# SCH_Nucleo__DAC8830_ADS8681_2022-10-27.net
KiCad netlist of a schematic drawn in EasyEDA
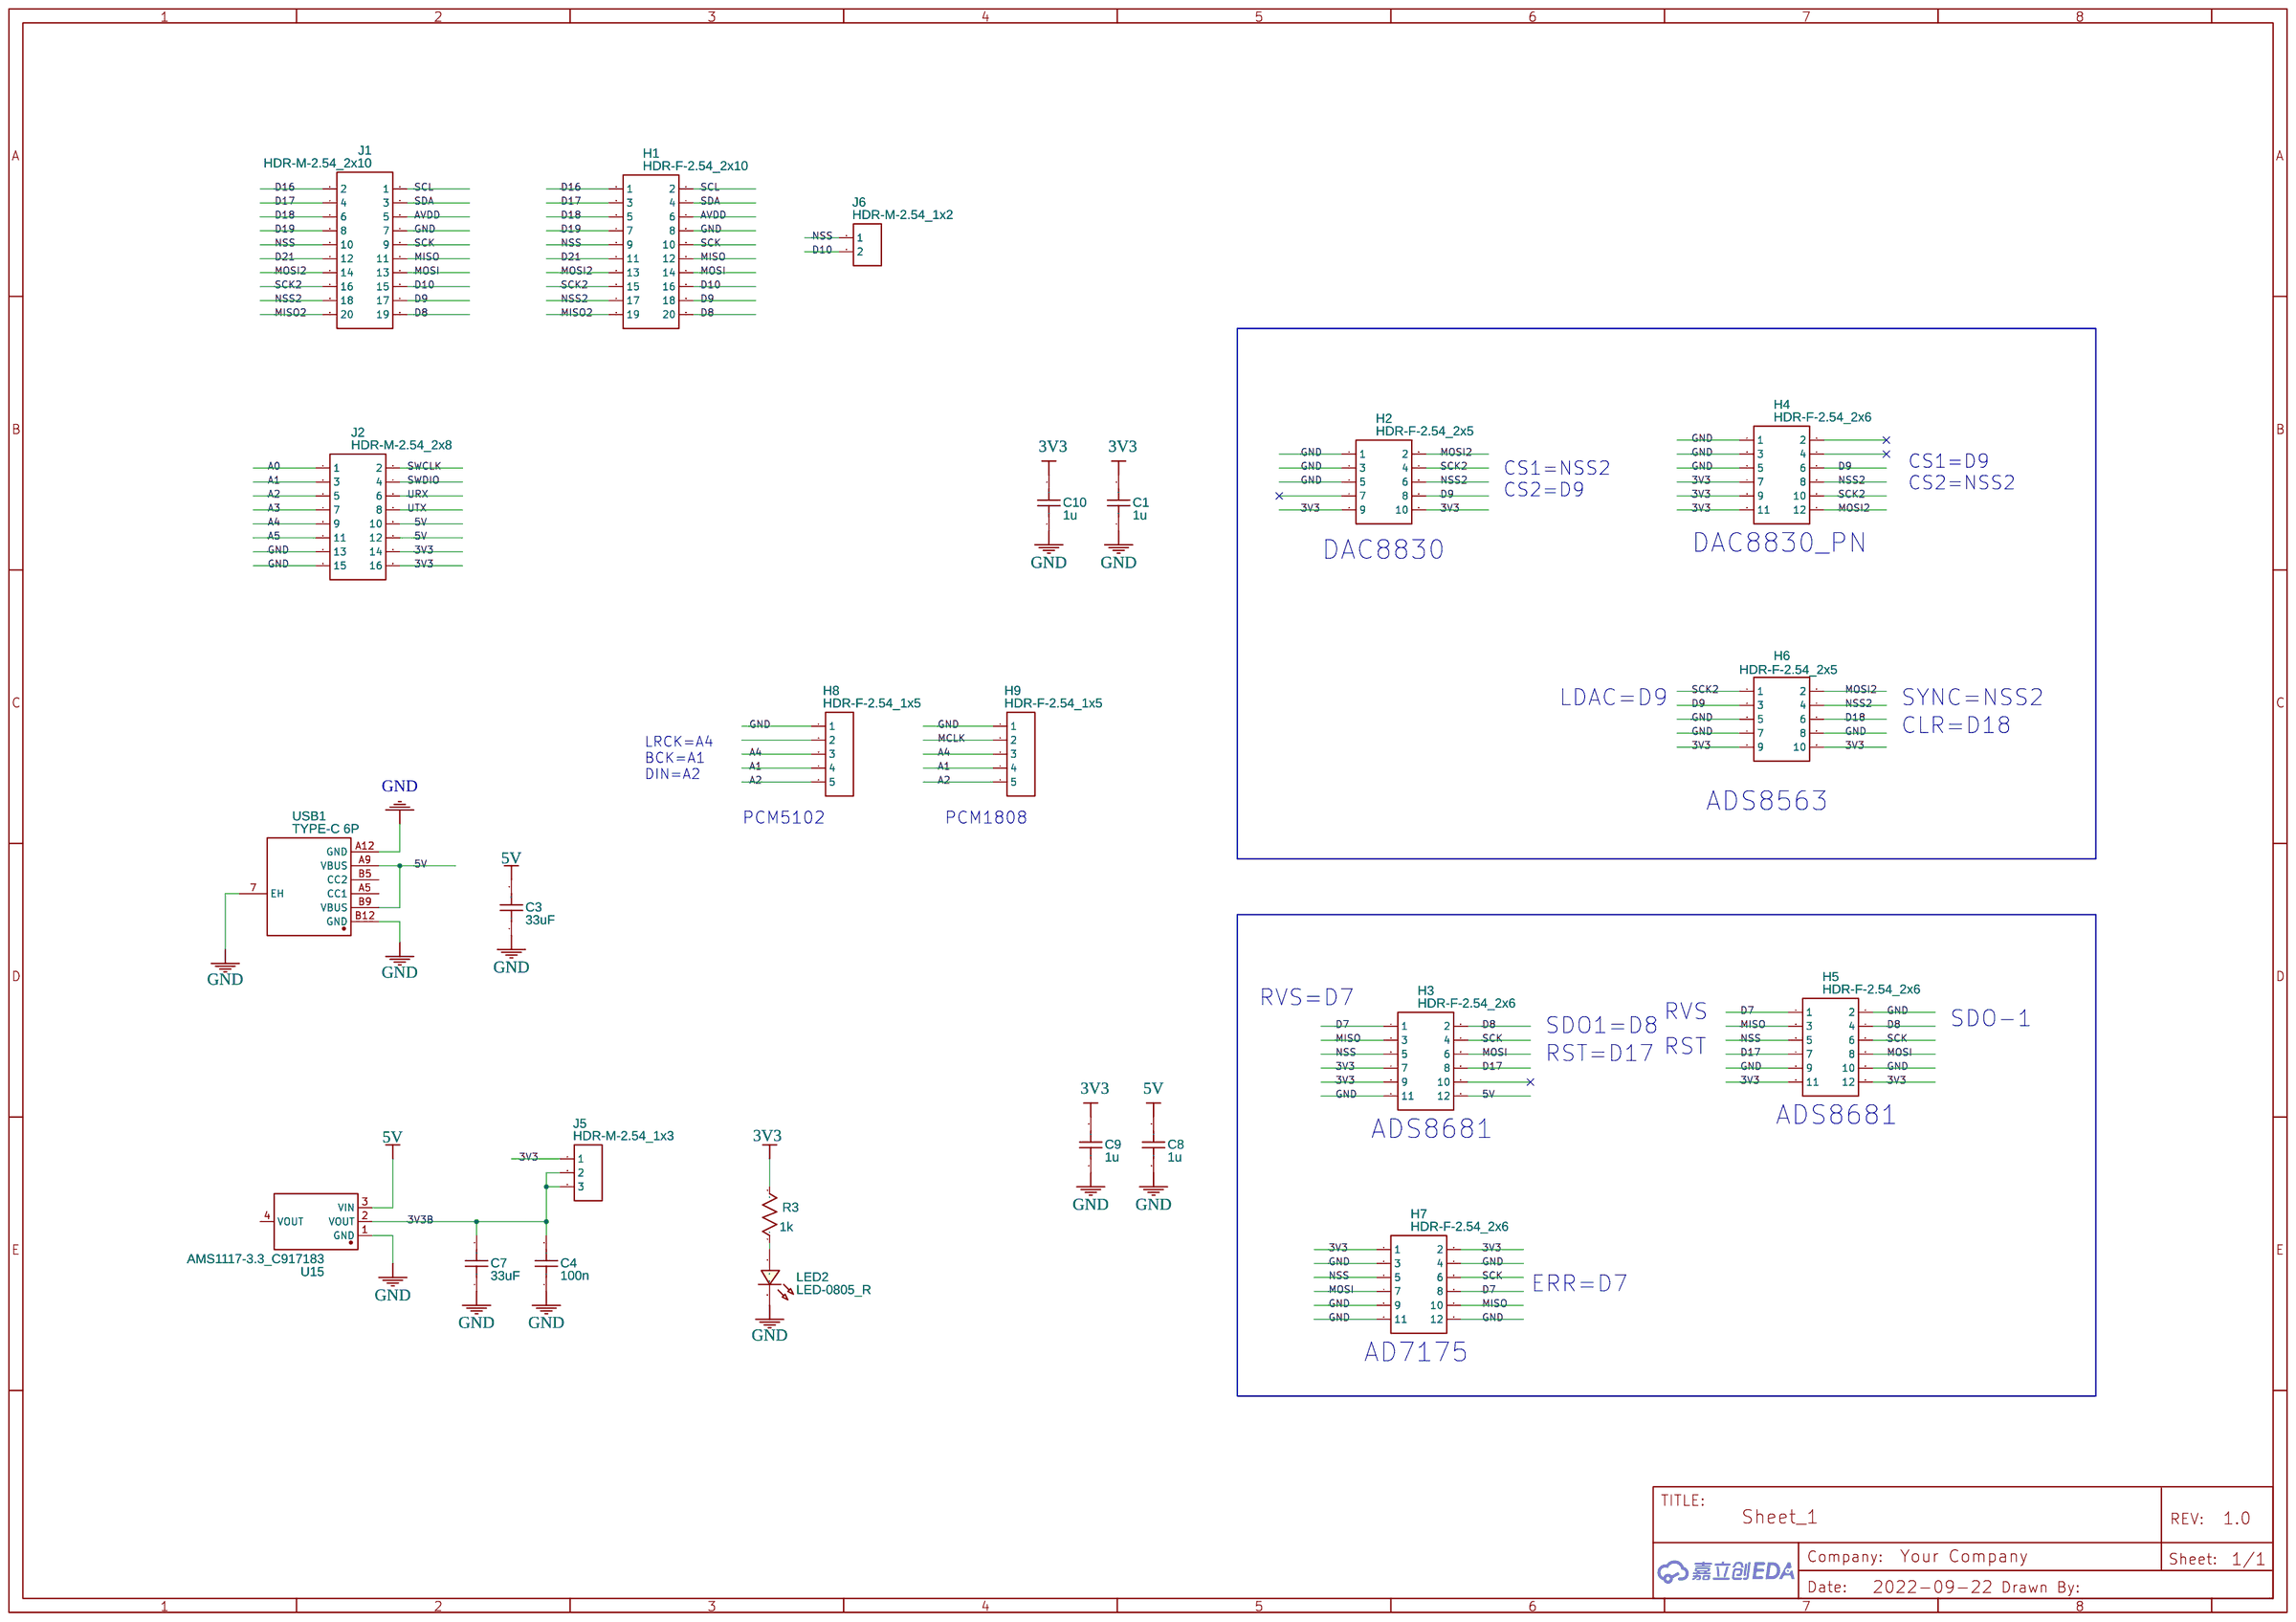
[diagram p0: 连接器]
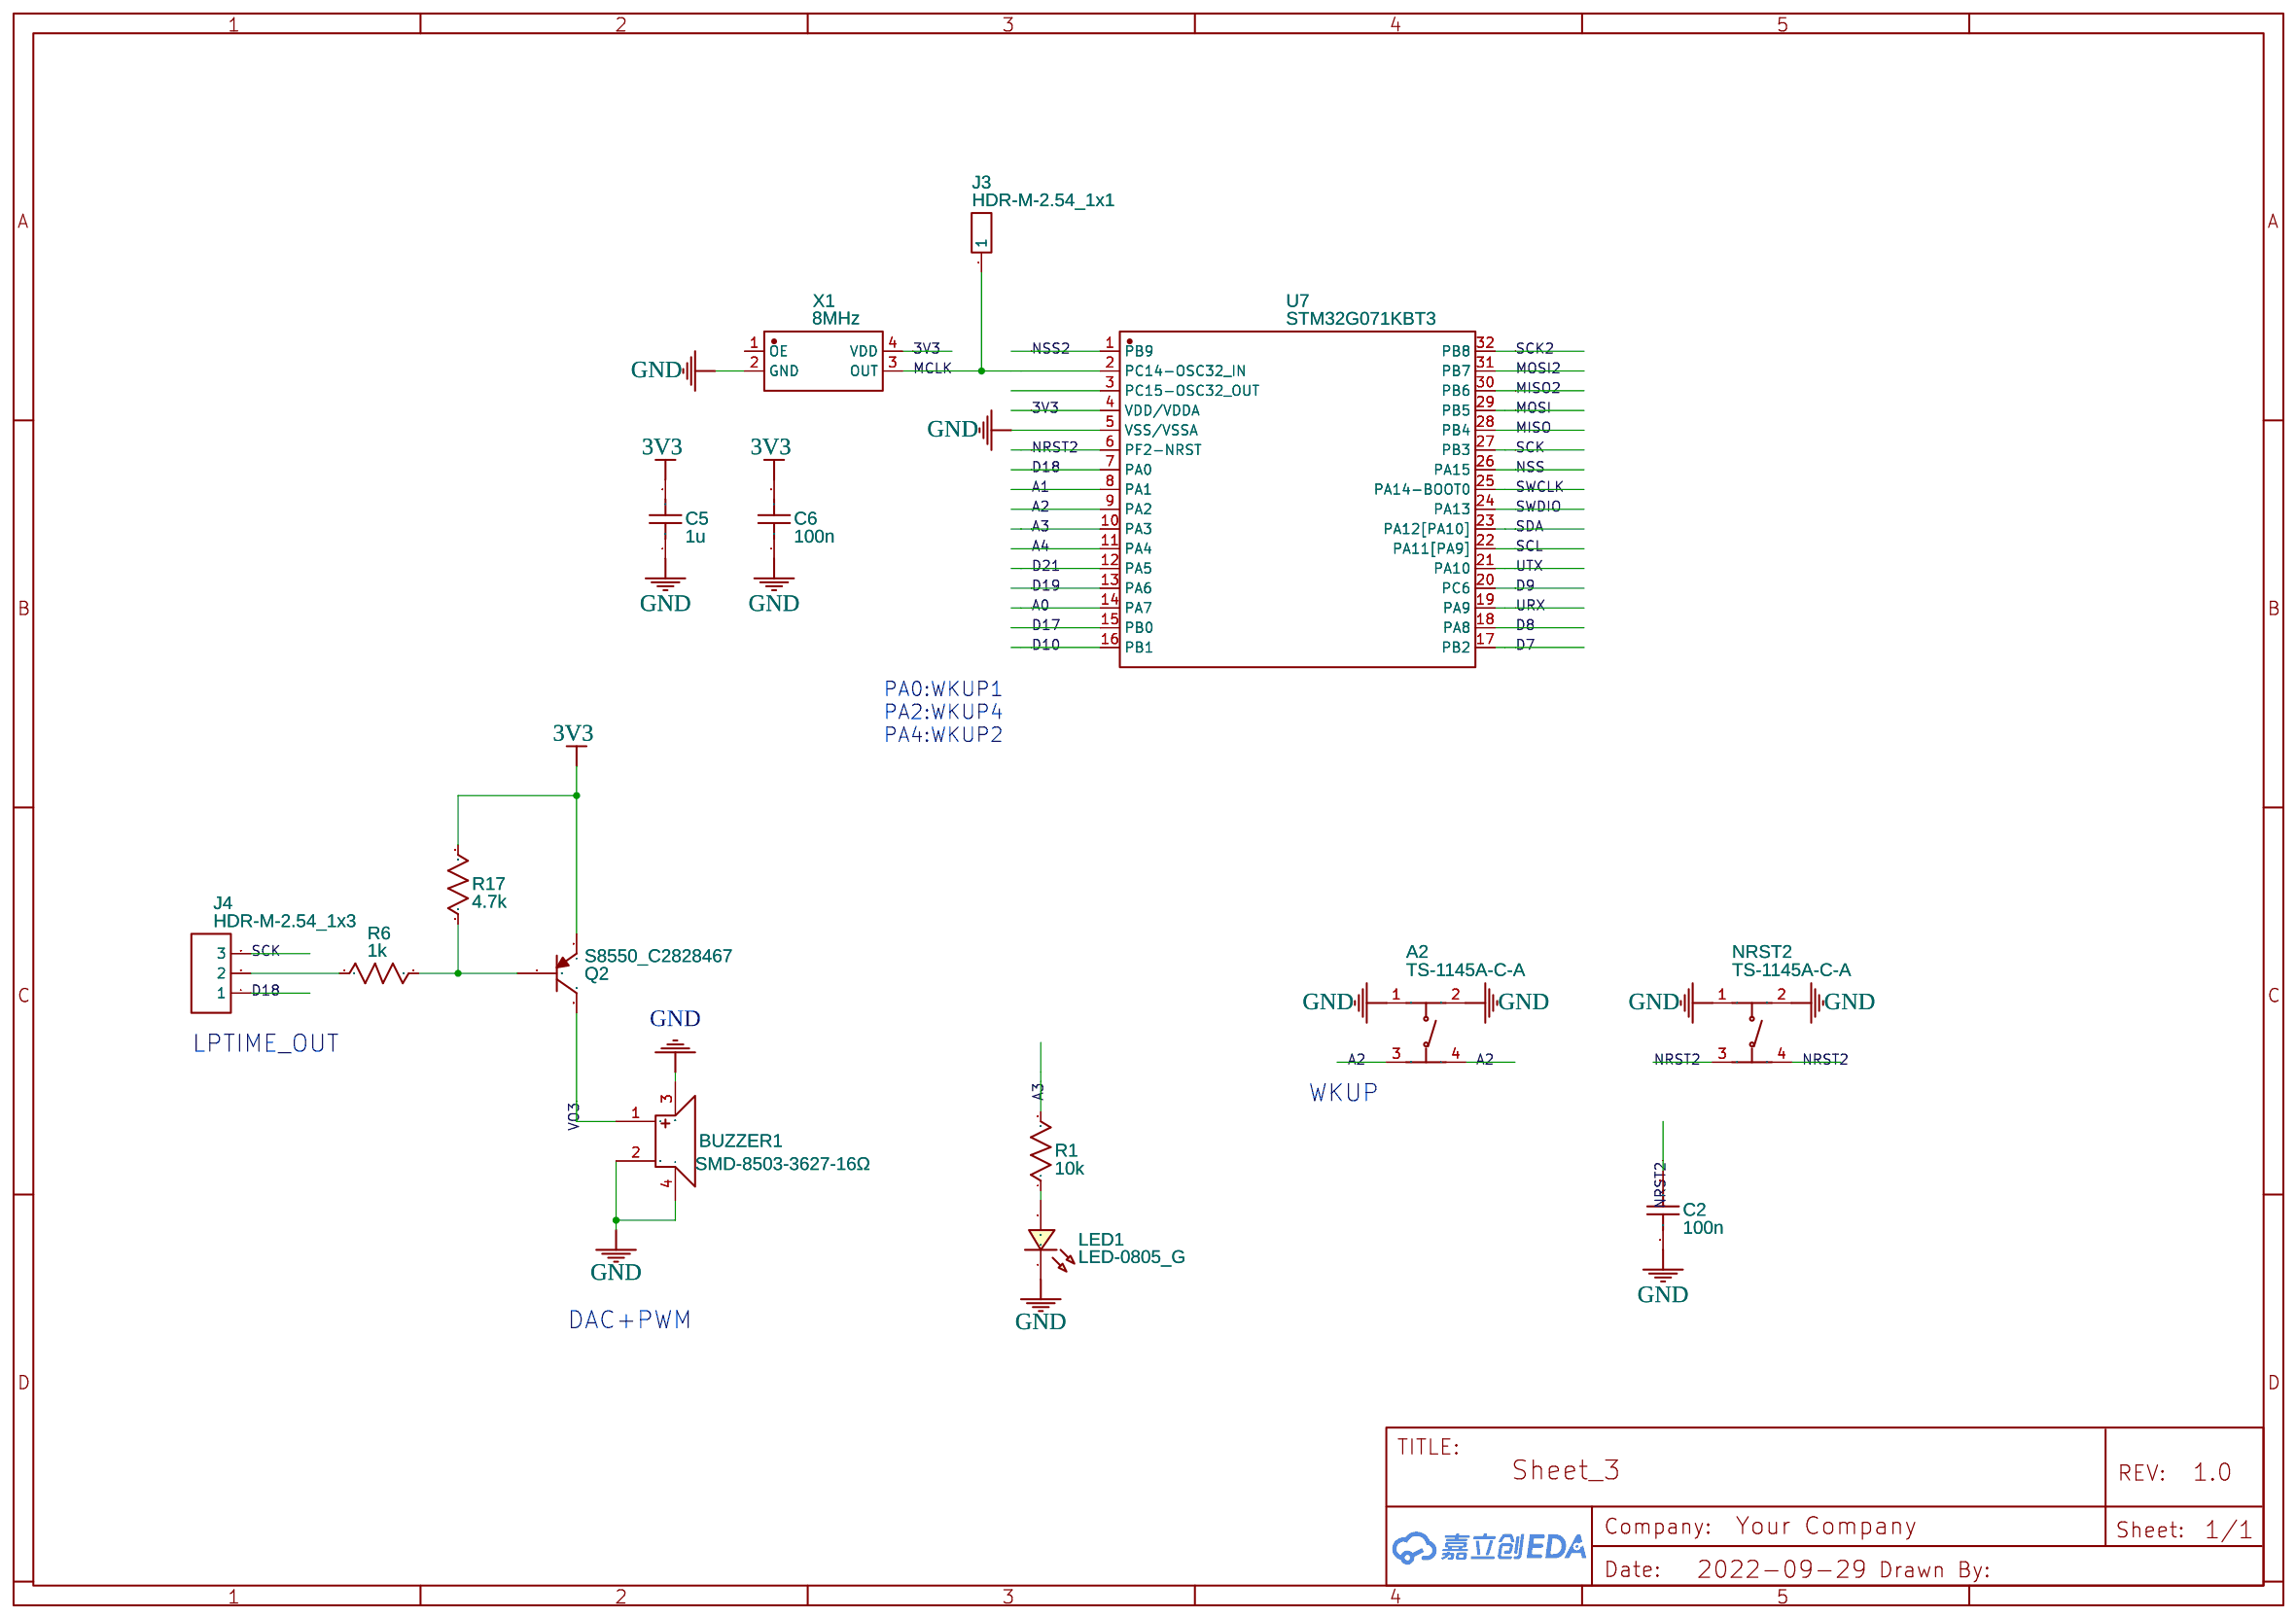
[diagram p1: mcu]

(export (version "E")
  (design (tool "Eeschema 10.0.6"))
  (components
    (comp (ref "C1")
      (value "1u")
      (fields
        (field (name "BOM_Manufacturer Part") "0805B105M500NT")
        (field (name "BOM_Supplier Part") "C2913555")
      )
      (libsource (lib "") (part "C_0805_US"))
    )
    (comp (ref "C3")
      (value "33uF")
      (fields
        (field (name "BOM_Manufacturer Part") "C3225X5R0J336MT0A0N")
        (field (name "BOM_Supplier Part") "C695362")
      )
      (libsource (lib "") (part "C3225X5R0J336MT0A0N"))
    )
    (comp (ref "C4") (value "100n") (libsource (lib "") (part "C_0805_US")))
    (comp (ref "C7")
      (value "33uF")
      (fields
        (field (name "BOM_Manufacturer Part") "C3225X5R0J336MT0A0N")
        (field (name "BOM_Supplier Part") "C695362")
      )
      (libsource (lib "") (part "C3225X5R0J336MT0A0N"))
    )
    (comp (ref "C8")
      (value "1u")
      (fields
        (field (name "BOM_Manufacturer Part") "0805B105M500NT")
        (field (name "BOM_Supplier Part") "C2913555")
      )
      (libsource (lib "") (part "C_0805_US"))
    )
    (comp (ref "C9")
      (value "1u")
      (fields
        (field (name "BOM_Manufacturer Part") "0805B105M500NT")
        (field (name "BOM_Supplier Part") "C2913555")
      )
      (libsource (lib "") (part "C_0805_US"))
    )
    (comp (ref "C10")
      (value "1u")
      (fields
        (field (name "BOM_Manufacturer Part") "0805B105M500NT")
        (field (name "BOM_Supplier Part") "C2913555")
      )
      (libsource (lib "") (part "C_0805_US"))
    )
    (comp (ref "H1")
      (value "HDR-F-2.54_2x10")
      (fields (field (name "BOM_Supplier Part") "C30867"))
      (libsource (lib "") (part "HDR-F-2.54_2x10"))
    )
    (comp (ref "H2")
      (value "HDR-F-2.54_2x5")
      (fields (field (name "BOM_Supplier Part") "C30419"))
      (libsource (lib "") (part "HDR-F-2.54_2x5"))
    )
    (comp (ref "H3")
      (value "HDR-F-2.54_2x6")
      (fields (field (name "BOM_Supplier Part") "C36191"))
      (libsource (lib "") (part "HDR-F-2.54_2x6"))
    )
    (comp (ref "H4")
      (value "HDR-F-2.54_2x6")
      (fields (field (name "BOM_Supplier Part") "C36191"))
      (libsource (lib "") (part "HDR-F-2.54_2x6"))
    )
    (comp (ref "H5")
      (value "HDR-F-2.54_2x6")
      (fields (field (name "BOM_Supplier Part") "C36191"))
      (libsource (lib "") (part "HDR-F-2.54_2x6"))
    )
    (comp (ref "H6")
      (value "HDR-F-2.54_2x5")
      (fields (field (name "BOM_Supplier Part") "C30419"))
      (libsource (lib "") (part "HDR-F-2.54_2x5"))
    )
    (comp (ref "H7")
      (value "HDR-F-2.54_2x6")
      (fields (field (name "BOM_Supplier Part") "C36191"))
      (libsource (lib "") (part "HDR-F-2.54_2x6"))
    )
    (comp (ref "H8")
      (value "HDR-F-2.54_1x5")
      (fields (field (name "BOM_Supplier Part") "C50950"))
      (libsource (lib "") (part "HDR-F-2.54_1x5"))
    )
    (comp (ref "H9")
      (value "HDR-F-2.54_1x5")
      (fields (field (name "BOM_Supplier Part") "C50950"))
      (libsource (lib "") (part "HDR-F-2.54_1x5"))
    )
    (comp (ref "J1")
      (value "HDR-M-2.54_2x10")
      (fields (field (name "BOM_Supplier Part") "C124359"))
      (libsource (lib "") (part "HDR-M-2.54_2x10"))
    )
    (comp (ref "J2")
      (value "HDR-M-2.54_2x8")
      (fields (field (name "BOM_Supplier Part") "C68234"))
      (libsource (lib "") (part "HDR-M-2.54_2x8"))
    )
    (comp (ref "J5")
      (value "HDR-M-2.54_1x3")
      (fields (field (name "BOM_Supplier Part") "C180248"))
      (libsource (lib "") (part "HDR-M-2.54_1x3"))
    )
    (comp (ref "J6")
      (value "HDR-M-2.54_1x2")
      (fields (field (name "BOM_Supplier Part") "C124375"))
      (libsource (lib "") (part "HDR-M-2.54_1x2"))
    )
    (comp (ref "LED2")
      (value "LED-0805_R")
      (fields
        (field (name "BOM_Manufacturer Part") "17-21SURC/S530-A3/TR8")
        (field (name "BOM_Supplier Part") "C72037")
      )
      (libsource (lib "") (part "LED-0805_R"))
    )
    (comp (ref "R3")
      (value "1k")
      (fields
        (field (name "BOM_Manufacturer Part") "TC0525F1001T5E")
        (field (name "BOM_Supplier Part") "C75781")
      )
      (libsource (lib "") (part "R_0805_US"))
    )
    (comp (ref "U15")
      (value "AMS1117-3.3_C917183")
      (fields
        (field (name "BOM_Manufacturer Part") "AMS1117-3.3")
        (field (name "BOM_Supplier Part") "C917183")
      )
      (libsource (lib "") (part "AMS1117-3.3_C917183"))
    )
    (comp (ref "USB1")
      (value "TYPE-C 6P")
      (fields (field (name "BOM_Supplier Part") "C456012"))
      (libsource (lib "") (part "TYPE-C 6P"))
    )
    (comp (ref "A2")
      (value "TS-1145A-C-A")
      (fields (field (name "BOM_Supplier Part") "C318903"))
      (libsource (lib "") (part "TS-1145A-C-A"))
    )
    (comp (ref "BUZZER1")
      (value "SMD-8503-3627-16Ω")
      (fields (field (name "BOM_Supplier Part") "C2685545"))
      (libsource (lib "") (part "SMD-8503-3627-16Ω"))
    )
    (comp (ref "C2")
      (value "100n")
      (fields
        (field (name "BOM_Manufacturer Part") "0805B105M500NT")
        (field (name "BOM_Supplier Part") "C2913555")
      )
      (libsource (lib "") (part "C_0805_US"))
    )
    (comp (ref "C5")
      (value "1u")
      (fields
        (field (name "BOM_Manufacturer Part") "0805B105M500NT")
        (field (name "BOM_Supplier Part") "C2913555")
      )
      (libsource (lib "") (part "C_0805_US"))
    )
    (comp (ref "C6")
      (value "100n")
      (fields
        (field (name "BOM_Manufacturer Part") "0805B105M500NT")
        (field (name "BOM_Supplier Part") "C2913555")
      )
      (libsource (lib "") (part "C_0805_US"))
    )
    (comp (ref "J3")
      (value "HDR-M-2.54_1x1")
      (fields (field (name "BOM_Supplier Part") "C81276"))
      (libsource (lib "") (part "HDR-M-2.54_1x1"))
    )
    (comp (ref "J4")
      (value "HDR-M-2.54_1x3")
      (fields (field (name "BOM_Supplier Part") "C180248"))
      (libsource (lib "") (part "HDR-M-2.54_1x3"))
    )
    (comp (ref "LED1")
      (value "LED-0805_G")
      (fields (field (name "BOM_Manufacturer Part") "NCD0805G1") (field (name "BOM_Supplier Part") "C84260"))
      (libsource (lib "") (part "LED-0805_G"))
    )
    (comp (ref "NRST2")
      (value "TS-1145A-C-A")
      (fields (field (name "BOM_Supplier Part") "C318903"))
      (libsource (lib "") (part "TS-1145A-C-A_1"))
    )
    (comp (ref "Q2")
      (value "S8550_C2828467")
      (fields (field (name "BOM_Manufacturer Part") "S8550") (field (name "BOM_Supplier Part") "C2828467"))
      (libsource (lib "") (part "S8550_C2828467"))
    )
    (comp (ref "R1")
      (value "10k")
      (fields
        (field (name "BOM_Manufacturer Part") "TC0525F1001T5E")
        (field (name "BOM_Supplier Part") "C75781")
      )
      (libsource (lib "") (part "R_0805_US"))
    )
    (comp (ref "R6") (value "1k") (libsource (lib "") (part "R_0805_US_1")))
    (comp (ref "R17") (value "4.7k") (libsource (lib "") (part "R_0805_US")))
    (comp (ref "U7")
      (value "STM32G071KBT3")
      (fields (field (name "BOM_Supplier Part") "C724238"))
      (libsource (lib "") (part "STM32G071KBT3"))
    )
    (comp (ref "X1")
      (value "8MHz")
      (fields
        (field (name "BOM_Manufacturer Part") "S2H008000I3CHE-T")
        (field (name "BOM_Supplier Part") "C253908")
      )
      (libsource (lib "") (part "S2H008000I3CHE-T"))
    )
  )
  (nets
    (net (code "1") (name "3V3") (class "Default")
      (node (ref "C1") (pin "2") (pinfunction "2_2") (pintype "unspecified"))
      (node (ref "C10") (pin "2") (pinfunction "2_2") (pintype "unspecified"))
      (node (ref "C5") (pin "2") (pinfunction "2_2") (pintype "unspecified"))
      (node (ref "C6") (pin "2") (pinfunction "2_2") (pintype "unspecified"))
      (node (ref "C9") (pin "2") (pinfunction "2_2") (pintype "unspecified"))
      (node (ref "H2") (pin "10") (pinfunction "10_10") (pintype "unspecified"))
      (node (ref "H2") (pin "9") (pinfunction "9_9") (pintype "unspecified"))
      (node (ref "H3") (pin "7") (pinfunction "7_7") (pintype "input"))
      (node (ref "H3") (pin "9") (pinfunction "9_9") (pintype "input"))
      (node (ref "H4") (pin "11") (pinfunction "11_11") (pintype "input"))
      (node (ref "H4") (pin "7") (pinfunction "7_7") (pintype "input"))
      (node (ref "H4") (pin "9") (pinfunction "9_9") (pintype "input"))
      (node (ref "H5") (pin "11") (pinfunction "11_11") (pintype "input"))
      (node (ref "H5") (pin "12") (pinfunction "12_12") (pintype "input"))
      (node (ref "H6") (pin "10") (pinfunction "10_10") (pintype "unspecified"))
      (node (ref "H6") (pin "9") (pinfunction "9_9") (pintype "unspecified"))
      (node (ref "H7") (pin "1") (pinfunction "1_1") (pintype "input"))
      (node (ref "H7") (pin "2") (pinfunction "2_2") (pintype "input"))
      (node (ref "J2") (pin "14") (pinfunction "14_14") (pintype "input"))
      (node (ref "J2") (pin "16") (pinfunction "16_16") (pintype "input"))
      (node (ref "J5") (pin "1") (pinfunction "1_1") (pintype "input"))
      (node (ref "Q2") (pin "2") (pinfunction "E_2") (pintype "unspecified"))
      (node (ref "R17") (pin "2") (pinfunction "2_2") (pintype "unspecified"))
      (node (ref "R3") (pin "2") (pinfunction "2_2") (pintype "unspecified"))
      (node (ref "U7") (pin "4") (pinfunction "VDD/VDDA_4") (pintype "unspecified"))
      (node (ref "X1") (pin "4") (pinfunction "VDD_4") (pintype "unspecified"))
    )
    (net (code "2") (name "3V3B") (class "Default")
      (node (ref "C4") (pin "2") (pinfunction "2_2") (pintype "unspecified"))
      (node (ref "C7") (pin "2") (pinfunction "2_2") (pintype "unspecified"))
      (node (ref "J5") (pin "2") (pinfunction "2_2") (pintype "input"))
      (node (ref "J5") (pin "3") (pinfunction "3_3") (pintype "input"))
      (node (ref "U15") (pin "2") (pinfunction "VOUT_2") (pintype "unspecified"))
    )
    (net (code "3") (name "5V") (class "Default")
      (node (ref "C3") (pin "2") (pinfunction "2_2") (pintype "unspecified"))
      (node (ref "C8") (pin "2") (pinfunction "2_2") (pintype "unspecified"))
      (node (ref "H3") (pin "12") (pinfunction "12_12") (pintype "input"))
      (node (ref "J2") (pin "10") (pinfunction "10_10") (pintype "input"))
      (node (ref "J2") (pin "12") (pinfunction "12_12") (pintype "input"))
      (node (ref "U15") (pin "3") (pinfunction "VIN_3") (pintype "unspecified"))
      (node (ref "USB1") (pin "A9") (pinfunction "VBUS_A9") (pintype "unspecified"))
      (node (ref "USB1") (pin "B9") (pinfunction "VBUS_B9") (pintype "unspecified"))
    )
    (net (code "4") (name "A0") (class "Default")
      (node (ref "J2") (pin "1") (pinfunction "1_1") (pintype "input"))
      (node (ref "U7") (pin "14") (pinfunction "PA7_14") (pintype "unspecified"))
    )
    (net (code "5") (name "A1") (class "Default")
      (node (ref "H8") (pin "4") (pinfunction "4_4") (pintype "unspecified"))
      (node (ref "H9") (pin "4") (pinfunction "4_4") (pintype "unspecified"))
      (node (ref "J2") (pin "3") (pinfunction "3_3") (pintype "input"))
      (node (ref "U7") (pin "8") (pinfunction "PA1_8") (pintype "unspecified"))
    )
    (net (code "6") (name "A2") (class "Default")
      (node (ref "A2") (pin "3") (pinfunction "3_3") (pintype "unspecified"))
      (node (ref "A2") (pin "4") (pinfunction "4_4") (pintype "unspecified"))
      (node (ref "H8") (pin "5") (pinfunction "5_5") (pintype "unspecified"))
      (node (ref "H9") (pin "5") (pinfunction "5_5") (pintype "unspecified"))
      (node (ref "J2") (pin "5") (pinfunction "5_5") (pintype "input"))
      (node (ref "U7") (pin "9") (pinfunction "PA2_9") (pintype "unspecified"))
    )
    (net (code "7") (name "A3") (class "Default")
      (node (ref "J2") (pin "7") (pinfunction "7_7") (pintype "input"))
      (node (ref "R1") (pin "2") (pinfunction "2_2") (pintype "unspecified"))
      (node (ref "U7") (pin "10") (pinfunction "PA3_10") (pintype "unspecified"))
    )
    (net (code "8") (name "A4") (class "Default")
      (node (ref "H8") (pin "3") (pinfunction "3_3") (pintype "unspecified"))
      (node (ref "H9") (pin "3") (pinfunction "3_3") (pintype "unspecified"))
      (node (ref "J2") (pin "9") (pinfunction "9_9") (pintype "input"))
      (node (ref "U7") (pin "11") (pinfunction "PA4_11") (pintype "unspecified"))
    )
    (net (code "9") (name "A5") (class "Default")
      (node (ref "J2") (pin "11") (pinfunction "11_11") (pintype "input"))
    )
    (net (code "10") (name "AVDD") (class "Default")
      (node (ref "H1") (pin "6") (pinfunction "6_6") (pintype "input"))
      (node (ref "J1") (pin "5") (pinfunction "5_5") (pintype "unspecified"))
    )
    (net (code "11") (name "D7") (class "Default")
      (node (ref "H3") (pin "1") (pinfunction "1_1") (pintype "input"))
      (node (ref "H5") (pin "1") (pinfunction "1_1") (pintype "input"))
      (node (ref "H7") (pin "8") (pinfunction "8_8") (pintype "input"))
      (node (ref "U7") (pin "17") (pinfunction "PB2_17") (pintype "unspecified"))
    )
    (net (code "12") (name "D8") (class "Default")
      (node (ref "H1") (pin "20") (pinfunction "20_20") (pintype "input"))
      (node (ref "H3") (pin "2") (pinfunction "2_2") (pintype "input"))
      (node (ref "H5") (pin "4") (pinfunction "4_4") (pintype "input"))
      (node (ref "J1") (pin "19") (pinfunction "19_19") (pintype "unspecified"))
      (node (ref "U7") (pin "18") (pinfunction "PA8_18") (pintype "unspecified"))
    )
    (net (code "13") (name "D9") (class "Default")
      (node (ref "H1") (pin "18") (pinfunction "18_18") (pintype "input"))
      (node (ref "H2") (pin "8") (pinfunction "8_8") (pintype "unspecified"))
      (node (ref "H4") (pin "6") (pinfunction "6_6") (pintype "input"))
      (node (ref "H6") (pin "3") (pinfunction "3_3") (pintype "unspecified"))
      (node (ref "J1") (pin "17") (pinfunction "17_17") (pintype "unspecified"))
      (node (ref "U7") (pin "20") (pinfunction "PC6_20") (pintype "unspecified"))
    )
    (net (code "14") (name "D10") (class "Default")
      (node (ref "H1") (pin "16") (pinfunction "16_16") (pintype "input"))
      (node (ref "J1") (pin "15") (pinfunction "15_15") (pintype "unspecified"))
      (node (ref "J6") (pin "2") (pinfunction "2_2") (pintype "unspecified"))
      (node (ref "U7") (pin "16") (pinfunction "PB1_16") (pintype "unspecified"))
    )
    (net (code "15") (name "D16") (class "Default")
      (node (ref "H1") (pin "1") (pinfunction "1_1") (pintype "input"))
      (node (ref "J1") (pin "2") (pinfunction "2_2") (pintype "unspecified"))
    )
    (net (code "16") (name "D17") (class "Default")
      (node (ref "H1") (pin "3") (pinfunction "3_3") (pintype "input"))
      (node (ref "H3") (pin "8") (pinfunction "8_8") (pintype "input"))
      (node (ref "H5") (pin "7") (pinfunction "7_7") (pintype "input"))
      (node (ref "J1") (pin "4") (pinfunction "4_4") (pintype "unspecified"))
      (node (ref "U7") (pin "15") (pinfunction "PB0_15") (pintype "unspecified"))
    )
    (net (code "17") (name "D18") (class "Default")
      (node (ref "H1") (pin "5") (pinfunction "5_5") (pintype "input"))
      (node (ref "H6") (pin "6") (pinfunction "6_6") (pintype "unspecified"))
      (node (ref "J1") (pin "6") (pinfunction "6_6") (pintype "unspecified"))
      (node (ref "J4") (pin "1") (pinfunction "1_1") (pintype "input"))
      (node (ref "U7") (pin "7") (pinfunction "PA0_7") (pintype "unspecified"))
    )
    (net (code "18") (name "D19") (class "Default")
      (node (ref "H1") (pin "7") (pinfunction "7_7") (pintype "input"))
      (node (ref "J1") (pin "8") (pinfunction "8_8") (pintype "unspecified"))
      (node (ref "U7") (pin "13") (pinfunction "PA6_13") (pintype "unspecified"))
    )
    (net (code "19") (name "D21") (class "Default")
      (node (ref "H1") (pin "11") (pinfunction "11_11") (pintype "input"))
      (node (ref "J1") (pin "12") (pinfunction "12_12") (pintype "unspecified"))
      (node (ref "U7") (pin "12") (pinfunction "PA5_12") (pintype "unspecified"))
    )
    (net (code "20") (name "GND") (class "Default")
      (node (ref "A2") (pin "1") (pinfunction "1_1") (pintype "unspecified"))
      (node (ref "A2") (pin "2") (pinfunction "2_2") (pintype "unspecified"))
      (node (ref "BUZZER1") (pin "2") (pinfunction "2_2") (pintype "unspecified"))
      (node (ref "BUZZER1") (pin "3") (pinfunction "3_3") (pintype "unspecified"))
      (node (ref "BUZZER1") (pin "4") (pinfunction "4_4") (pintype "unspecified"))
      (node (ref "C1") (pin "1") (pinfunction "1_1") (pintype "unspecified"))
      (node (ref "C10") (pin "1") (pinfunction "1_1") (pintype "unspecified"))
      (node (ref "C2") (pin "1") (pinfunction "1_1") (pintype "unspecified"))
      (node (ref "C3") (pin "1") (pinfunction "1_1") (pintype "unspecified"))
      (node (ref "C4") (pin "1") (pinfunction "1_1") (pintype "unspecified"))
      (node (ref "C5") (pin "1") (pinfunction "1_1") (pintype "unspecified"))
      (node (ref "C6") (pin "1") (pinfunction "1_1") (pintype "unspecified"))
      (node (ref "C7") (pin "1") (pinfunction "1_1") (pintype "unspecified"))
      (node (ref "C8") (pin "1") (pinfunction "1_1") (pintype "unspecified"))
      (node (ref "C9") (pin "1") (pinfunction "1_1") (pintype "unspecified"))
      (node (ref "H1") (pin "8") (pinfunction "8_8") (pintype "input"))
      (node (ref "H2") (pin "1") (pinfunction "1_1") (pintype "unspecified"))
      (node (ref "H2") (pin "3") (pinfunction "3_3") (pintype "unspecified"))
      (node (ref "H2") (pin "5") (pinfunction "5_5") (pintype "unspecified"))
      (node (ref "H3") (pin "11") (pinfunction "11_11") (pintype "input"))
      (node (ref "H4") (pin "1") (pinfunction "1_1") (pintype "input"))
      (node (ref "H4") (pin "3") (pinfunction "3_3") (pintype "input"))
      (node (ref "H4") (pin "5") (pinfunction "5_5") (pintype "input"))
      (node (ref "H5") (pin "10") (pinfunction "10_10") (pintype "input"))
      (node (ref "H5") (pin "2") (pinfunction "2_2") (pintype "input"))
      (node (ref "H5") (pin "9") (pinfunction "9_9") (pintype "input"))
      (node (ref "H6") (pin "5") (pinfunction "5_5") (pintype "unspecified"))
      (node (ref "H6") (pin "7") (pinfunction "7_7") (pintype "unspecified"))
      (node (ref "H6") (pin "8") (pinfunction "8_8") (pintype "unspecified"))
      (node (ref "H7") (pin "11") (pinfunction "11_11") (pintype "input"))
      (node (ref "H7") (pin "12") (pinfunction "12_12") (pintype "input"))
      (node (ref "H7") (pin "3") (pinfunction "3_3") (pintype "input"))
      (node (ref "H7") (pin "4") (pinfunction "4_4") (pintype "input"))
      (node (ref "H7") (pin "9") (pinfunction "9_9") (pintype "input"))
      (node (ref "H8") (pin "1") (pinfunction "1_1") (pintype "unspecified"))
      (node (ref "H9") (pin "1") (pinfunction "1_1") (pintype "unspecified"))
      (node (ref "J1") (pin "7") (pinfunction "7_7") (pintype "unspecified"))
      (node (ref "J2") (pin "13") (pinfunction "13_13") (pintype "input"))
      (node (ref "J2") (pin "15") (pinfunction "15_15") (pintype "input"))
      (node (ref "LED1") (pin "2") (pinfunction "2_2") (pintype "unspecified"))
      (node (ref "LED2") (pin "2") (pinfunction "2_2") (pintype "unspecified"))
      (node (ref "NRST2") (pin "1") (pinfunction "1_1") (pintype "unspecified"))
      (node (ref "NRST2") (pin "2") (pinfunction "2_2") (pintype "unspecified"))
      (node (ref "U15") (pin "1") (pinfunction "GND_1") (pintype "unspecified"))
      (node (ref "U7") (pin "5") (pinfunction "VSS/VSSA_5") (pintype "unspecified"))
      (node (ref "USB1") (pin "7") (pinfunction "EH_7") (pintype "unspecified"))
      (node (ref "USB1") (pin "A12") (pinfunction "GND_A12") (pintype "unspecified"))
      (node (ref "USB1") (pin "B12") (pinfunction "GND_B12") (pintype "unspecified"))
      (node (ref "X1") (pin "2") (pinfunction "GND_2") (pintype "unspecified"))
    )
    (net (code "21") (name "MCLK") (class "Default")
      (node (ref "H9") (pin "2") (pinfunction "2_2") (pintype "unspecified"))
      (node (ref "J3") (pin "1") (pinfunction "1_1") (pintype "input"))
      (node (ref "U7") (pin "2") (pinfunction "PC14-OSC32_IN_2") (pintype "unspecified"))
      (node (ref "X1") (pin "3") (pinfunction "OUT_3") (pintype "unspecified"))
    )
    (net (code "22") (name "MISO") (class "Default")
      (node (ref "H1") (pin "12") (pinfunction "12_12") (pintype "input"))
      (node (ref "H3") (pin "3") (pinfunction "3_3") (pintype "input"))
      (node (ref "H5") (pin "3") (pinfunction "3_3") (pintype "input"))
      (node (ref "H7") (pin "10") (pinfunction "10_10") (pintype "input"))
      (node (ref "J1") (pin "11") (pinfunction "11_11") (pintype "unspecified"))
      (node (ref "U7") (pin "28") (pinfunction "PB4_28") (pintype "unspecified"))
    )
    (net (code "23") (name "MISO2") (class "Default")
      (node (ref "H1") (pin "19") (pinfunction "19_19") (pintype "input"))
      (node (ref "J1") (pin "20") (pinfunction "20_20") (pintype "unspecified"))
      (node (ref "U7") (pin "30") (pinfunction "PB6_30") (pintype "unspecified"))
    )
    (net (code "24") (name "MOSI") (class "Default")
      (node (ref "H1") (pin "14") (pinfunction "14_14") (pintype "input"))
      (node (ref "H3") (pin "6") (pinfunction "6_6") (pintype "input"))
      (node (ref "H5") (pin "8") (pinfunction "8_8") (pintype "input"))
      (node (ref "H7") (pin "7") (pinfunction "7_7") (pintype "input"))
      (node (ref "J1") (pin "13") (pinfunction "13_13") (pintype "unspecified"))
      (node (ref "U7") (pin "29") (pinfunction "PB5_29") (pintype "unspecified"))
    )
    (net (code "25") (name "MOSI2") (class "Default")
      (node (ref "H1") (pin "13") (pinfunction "13_13") (pintype "input"))
      (node (ref "H2") (pin "2") (pinfunction "2_2") (pintype "unspecified"))
      (node (ref "H4") (pin "12") (pinfunction "12_12") (pintype "input"))
      (node (ref "H6") (pin "2") (pinfunction "2_2") (pintype "unspecified"))
      (node (ref "J1") (pin "14") (pinfunction "14_14") (pintype "unspecified"))
      (node (ref "U7") (pin "31") (pinfunction "PB7_31") (pintype "unspecified"))
    )
    (net (code "26") (name "NRST2") (class "Default")
      (node (ref "C2") (pin "2") (pinfunction "2_2") (pintype "unspecified"))
      (node (ref "NRST2") (pin "3") (pinfunction "3_3") (pintype "unspecified"))
      (node (ref "NRST2") (pin "4") (pinfunction "4_4") (pintype "unspecified"))
      (node (ref "U7") (pin "6") (pinfunction "PF2-NRST_6") (pintype "unspecified"))
    )
    (net (code "27") (name "NSS") (class "Default")
      (node (ref "H1") (pin "9") (pinfunction "9_9") (pintype "input"))
      (node (ref "H3") (pin "5") (pinfunction "5_5") (pintype "input"))
      (node (ref "H5") (pin "5") (pinfunction "5_5") (pintype "input"))
      (node (ref "H7") (pin "5") (pinfunction "5_5") (pintype "input"))
      (node (ref "J1") (pin "10") (pinfunction "10_10") (pintype "unspecified"))
      (node (ref "J6") (pin "1") (pinfunction "1_1") (pintype "unspecified"))
      (node (ref "U7") (pin "26") (pinfunction "PA15_26") (pintype "unspecified"))
    )
    (net (code "28") (name "NSS2") (class "Default")
      (node (ref "H1") (pin "17") (pinfunction "17_17") (pintype "input"))
      (node (ref "H2") (pin "6") (pinfunction "6_6") (pintype "unspecified"))
      (node (ref "H4") (pin "8") (pinfunction "8_8") (pintype "input"))
      (node (ref "H6") (pin "4") (pinfunction "4_4") (pintype "unspecified"))
      (node (ref "J1") (pin "18") (pinfunction "18_18") (pintype "unspecified"))
      (node (ref "U7") (pin "1") (pinfunction "PB9_1") (pintype "unspecified"))
    )
    (net (code "29") (name "Net-(J4-Pad2)") (class "Default")
      (node (ref "J4") (pin "2") (pinfunction "2_2") (pintype "input"))
      (node (ref "R6") (pin "1") (pinfunction "1_1") (pintype "unspecified"))
    )
    (net (code "30") (name "Net-(LED1-Pad1)") (class "Default")
      (node (ref "LED1") (pin "1") (pinfunction "1_1") (pintype "unspecified"))
      (node (ref "R1") (pin "1") (pinfunction "1_1") (pintype "unspecified"))
    )
    (net (code "31") (name "Net-(LED2-Pad1)") (class "Default")
      (node (ref "LED2") (pin "1") (pinfunction "1_1") (pintype "unspecified"))
      (node (ref "R3") (pin "1") (pinfunction "1_1") (pintype "unspecified"))
    )
    (net (code "32") (name "Net-(Q2-B)") (class "Default")
      (node (ref "Q2") (pin "1") (pinfunction "B_1") (pintype "unspecified"))
      (node (ref "R17") (pin "1") (pinfunction "1_1") (pintype "unspecified"))
      (node (ref "R6") (pin "2") (pinfunction "2_2") (pintype "unspecified"))
    )
    (net (code "33") (name "SCK") (class "Default")
      (node (ref "H1") (pin "10") (pinfunction "10_10") (pintype "input"))
      (node (ref "H3") (pin "4") (pinfunction "4_4") (pintype "input"))
      (node (ref "H5") (pin "6") (pinfunction "6_6") (pintype "input"))
      (node (ref "H7") (pin "6") (pinfunction "6_6") (pintype "input"))
      (node (ref "J1") (pin "9") (pinfunction "9_9") (pintype "unspecified"))
      (node (ref "J4") (pin "3") (pinfunction "3_3") (pintype "input"))
      (node (ref "U7") (pin "27") (pinfunction "PB3_27") (pintype "unspecified"))
    )
    (net (code "34") (name "SCK2") (class "Default")
      (node (ref "H1") (pin "15") (pinfunction "15_15") (pintype "input"))
      (node (ref "H2") (pin "4") (pinfunction "4_4") (pintype "unspecified"))
      (node (ref "H4") (pin "10") (pinfunction "10_10") (pintype "input"))
      (node (ref "H6") (pin "1") (pinfunction "1_1") (pintype "unspecified"))
      (node (ref "J1") (pin "16") (pinfunction "16_16") (pintype "unspecified"))
      (node (ref "U7") (pin "32") (pinfunction "PB8_32") (pintype "unspecified"))
    )
    (net (code "35") (name "SCL") (class "Default")
      (node (ref "H1") (pin "2") (pinfunction "2_2") (pintype "input"))
      (node (ref "J1") (pin "1") (pinfunction "1_1") (pintype "unspecified"))
      (node (ref "U7") (pin "22") (pinfunction "PA11[PA9]_22") (pintype "unspecified"))
    )
    (net (code "36") (name "SDA") (class "Default")
      (node (ref "H1") (pin "4") (pinfunction "4_4") (pintype "input"))
      (node (ref "J1") (pin "3") (pinfunction "3_3") (pintype "unspecified"))
      (node (ref "U7") (pin "23") (pinfunction "PA12[PA10]_23") (pintype "unspecified"))
    )
    (net (code "37") (name "SWCLK") (class "Default")
      (node (ref "J2") (pin "2") (pinfunction "2_2") (pintype "input"))
      (node (ref "U7") (pin "25") (pinfunction "PA14-BOOT0_25") (pintype "unspecified"))
    )
    (net (code "38") (name "SWDIO") (class "Default")
      (node (ref "J2") (pin "4") (pinfunction "4_4") (pintype "input"))
      (node (ref "U7") (pin "24") (pinfunction "PA13_24") (pintype "unspecified"))
    )
    (net (code "39") (name "URX") (class "Default")
      (node (ref "J2") (pin "6") (pinfunction "6_6") (pintype "input"))
      (node (ref "U7") (pin "19") (pinfunction "PA9_19") (pintype "unspecified"))
    )
    (net (code "40") (name "UTX") (class "Default")
      (node (ref "J2") (pin "8") (pinfunction "8_8") (pintype "input"))
      (node (ref "U7") (pin "21") (pinfunction "PA10_21") (pintype "unspecified"))
    )
    (net (code "41") (name "VO3") (class "Default")
      (node (ref "BUZZER1") (pin "1") (pinfunction "1_1") (pintype "unspecified"))
      (node (ref "Q2") (pin "3") (pinfunction "C_3") (pintype "unspecified"))
    )
    (net (code "42") (name "unconnected-(H2-Pad7)") (class "Default")
      (node (ref "H2") (pin "7") (pinfunction "7_7") (pintype "unspecified+no_connect"))
    )
    (net (code "43") (name "unconnected-(H3-Pad10)") (class "Default")
      (node (ref "H3") (pin "10") (pinfunction "10_10") (pintype "input+no_connect"))
    )
    (net (code "44") (name "unconnected-(H4-Pad2)") (class "Default")
      (node (ref "H4") (pin "2") (pinfunction "2_2") (pintype "input+no_connect"))
    )
    (net (code "45") (name "unconnected-(H4-Pad4)") (class "Default")
      (node (ref "H4") (pin "4") (pinfunction "4_4") (pintype "input+no_connect"))
    )
    (net (code "46") (name "unconnected-(H8-Pad2)") (class "Default")
      (node (ref "H8") (pin "2") (pinfunction "2_2") (pintype "unspecified"))
    )
    (net (code "47") (name "unconnected-(U7-PC15-OSC32_OUT-Pad3)") (class "Default")
      (node (ref "U7") (pin "3") (pinfunction "PC15-OSC32_OUT_3") (pintype "unspecified"))
    )
    (net (code "48") (name "unconnected-(U15-VOUT-Pad4)") (class "Default")
      (node (ref "U15") (pin "4") (pinfunction "VOUT_4") (pintype "unspecified"))
    )
    (net (code "49") (name "unconnected-(USB1-CC1-PadA5)") (class "Default")
      (node (ref "USB1") (pin "A5") (pinfunction "CC1_A5") (pintype "unspecified"))
    )
    (net (code "50") (name "unconnected-(USB1-CC2-PadB5)") (class "Default")
      (node (ref "USB1") (pin "B5") (pinfunction "CC2_B5") (pintype "unspecified"))
    )
    (net (code "51") (name "unconnected-(X1-OE-Pad1)") (class "Default")
      (node (ref "X1") (pin "1") (pinfunction "OE_1") (pintype "unspecified"))
    )
  )
)
